# FluxamasynthParticleTeensy.net
KiCad netlist of a schematic drawn in EAGLE
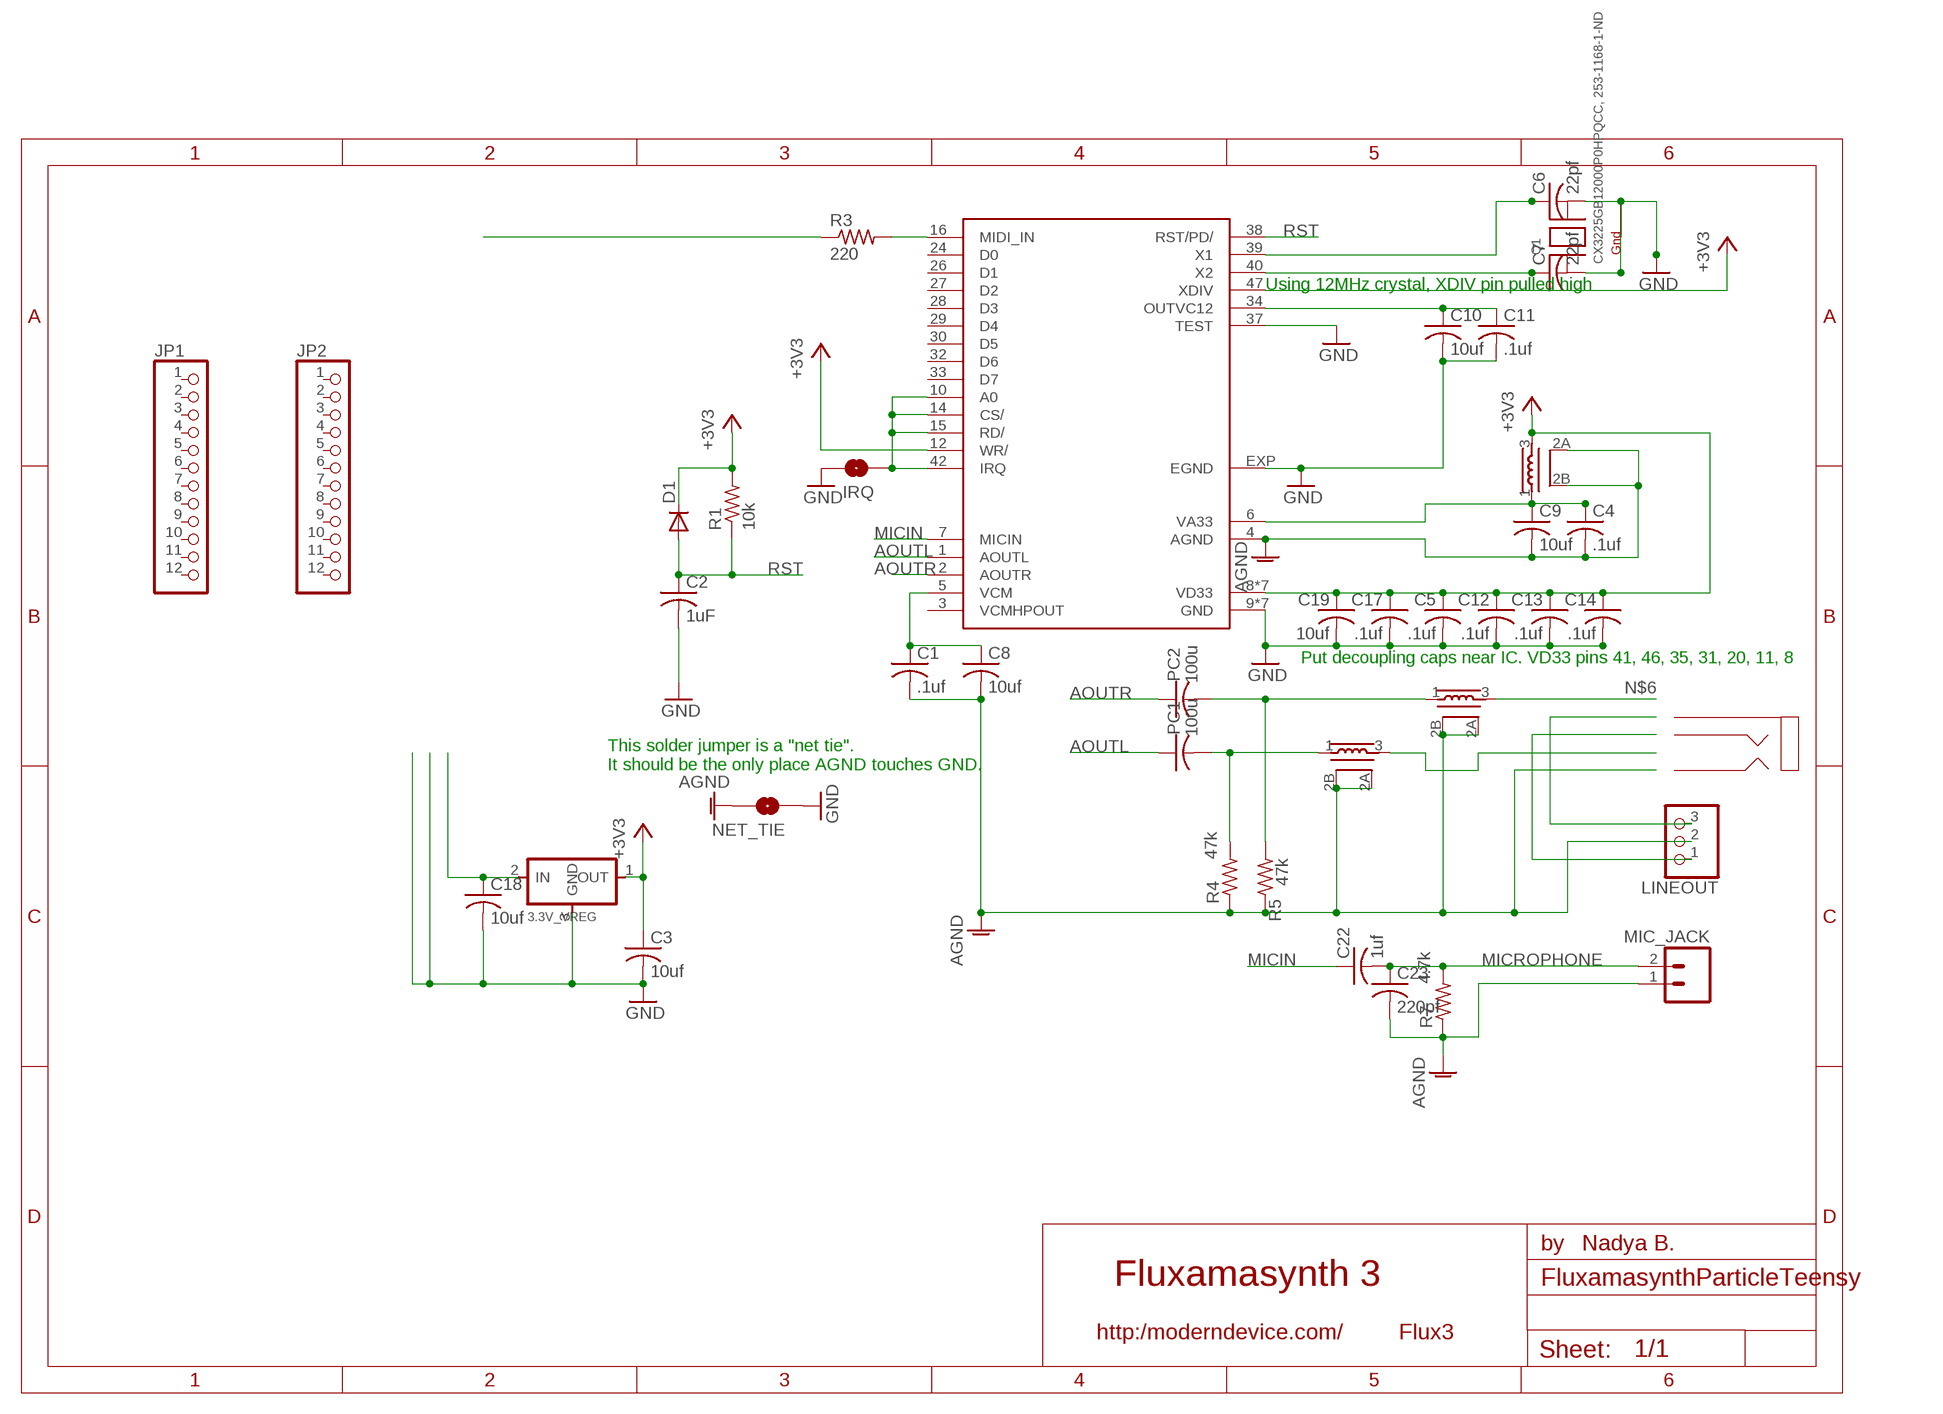
[diagram p0: schematic, sheet 1]

(export (version "E")
  (design (tool "Eeschema 10.0.6"))
  (components
    (comp (ref "3.3V_VREG")
      (value "REGULATORSOT23")
      (footprint "eagle-import:SOT23")
      (libsource (lib "eagle-import") (part "REGULATORSOT23"))
    )
    (comp (ref "C1")
      (value ".1uf")
      (footprint "eagle-import:C0603K")
      (libsource (lib "eagle-import") (part "rcl_C-USC0603K"))
    )
    (comp (ref "C2")
      (value "1uF")
      (footprint "eagle-import:C0805")
      (libsource (lib "eagle-import") (part "rcl_C-USC0805"))
    )
    (comp (ref "C3")
      (value "10uf")
      (footprint "eagle-import:C1206K")
      (libsource (lib "eagle-import") (part "C-USC1206K"))
    )
    (comp (ref "C4")
      (value ".1uf")
      (footprint "eagle-import:C0603K")
      (libsource (lib "eagle-import") (part "rcl_C-USC0603K"))
    )
    (comp (ref "C5")
      (value ".1uf")
      (footprint "eagle-import:C0603K")
      (libsource (lib "eagle-import") (part "rcl_C-USC0603K"))
    )
    (comp (ref "C6")
      (value "22pf")
      (footprint "eagle-import:C0805")
      (libsource (lib "eagle-import") (part "rcl_C-USC0805"))
    )
    (comp (ref "C7")
      (value "22pf")
      (footprint "eagle-import:C0805")
      (libsource (lib "eagle-import") (part "rcl_C-USC0805"))
    )
    (comp (ref "C8")
      (value "10uf")
      (footprint "eagle-import:C0805")
      (libsource (lib "eagle-import") (part "rcl_C-USC0805"))
    )
    (comp (ref "C9")
      (value "10uf")
      (footprint "eagle-import:C0805")
      (libsource (lib "eagle-import") (part "rcl_C-USC0805"))
    )
    (comp (ref "C10")
      (value "10uf")
      (footprint "eagle-import:C0805")
      (libsource (lib "eagle-import") (part "rcl_C-USC0805"))
    )
    (comp (ref "C11")
      (value ".1uf")
      (footprint "eagle-import:C0603K")
      (libsource (lib "eagle-import") (part "rcl_C-USC0603K"))
    )
    (comp (ref "C12")
      (value ".1uf")
      (footprint "eagle-import:C0603K")
      (libsource (lib "eagle-import") (part "rcl_C-USC0603K"))
    )
    (comp (ref "C13")
      (value ".1uf")
      (footprint "eagle-import:C0603K")
      (libsource (lib "eagle-import") (part "rcl_C-USC0603K"))
    )
    (comp (ref "C14")
      (value ".1uf")
      (footprint "eagle-import:C0603K")
      (libsource (lib "eagle-import") (part "rcl_C-USC0603K"))
    )
    (comp (ref "C17")
      (value ".1uf")
      (footprint "eagle-import:C0603K")
      (libsource (lib "eagle-import") (part "rcl_C-USC0603K"))
    )
    (comp (ref "C18")
      (value "10uf")
      (footprint "eagle-import:C1206K")
      (libsource (lib "eagle-import") (part "C-USC1206K"))
    )
    (comp (ref "C19")
      (value "10uf")
      (footprint "eagle-import:C0805")
      (libsource (lib "eagle-import") (part "rcl_C-USC0805"))
    )
    (comp (ref "C22")
      (value "1uf")
      (footprint "eagle-import:C0805")
      (libsource (lib "eagle-import") (part "rcl_C-USC0805"))
    )
    (comp (ref "C23")
      (value "220pf")
      (footprint "eagle-import:C0805")
      (libsource (lib "eagle-import") (part "rcl_C-USC0805"))
    )
    (comp (ref "D1")
      (value "DIODESOD123")
      (footprint "eagle-import:SOD123")
      (libsource (lib "eagle-import") (part "DIODESOD123"))
    )
    (comp (ref "IRQ")
      (value "MODERNDEVICE_SOLDERJUMPERTRACE")
      (footprint "eagle-import:MODERNDEVICE_SJ_2S-TRACE")
      (libsource (lib "eagle-import") (part "MODERNDEVICE_SOLDERJUMPERTRACE"))
    )
    (comp (ref "JP1")
      (value "PINHD-1X12-CB")
      (footprint "eagle-import:1X12-CB")
      (libsource (lib "eagle-import") (part "PINHD-1X12-CB"))
    )
    (comp (ref "JP2")
      (value "PINHD-1X12-CB")
      (footprint "eagle-import:1X12-CB")
      (libsource (lib "eagle-import") (part "PINHD-1X12-CB"))
    )
    (comp (ref "LINEOUT")
      (value "PINHD-1X3")
      (footprint "eagle-import:1X03")
      (libsource (lib "eagle-import") (part "PINHD-1X3"))
    )
    (comp (ref "MIC_JACK")
      (value "M02PTH")
      (footprint "eagle-import:1X02")
      (libsource (lib "eagle-import") (part "M02PTH"))
    )
    (comp (ref "NET_TIE")
      (value "MODERNDEVICE_SOLDERJUMPERTRACE")
      (footprint "eagle-import:MODERNDEVICE_SJ_2S-TRACE")
      (libsource (lib "eagle-import") (part "MODERNDEVICE_SOLDERJUMPERTRACE"))
    )
    (comp (ref "PC1")
      (value "100u")
      (footprint "eagle-import:C1206K")
      (libsource (lib "eagle-import") (part "C-USC1206K"))
    )
    (comp (ref "PC2")
      (value "100u")
      (footprint "eagle-import:C1206K")
      (libsource (lib "eagle-import") (part "C-USC1206K"))
    )
    (comp (ref "Q1")
      (value "CX3225GB12000P0HPQCC, 253-1168-1-ND")
      (footprint "eagle-import:MODERNDEVICE_NX3225")
      (libsource (lib "eagle-import") (part "MODERNDEVICE_XTAL-4-3225"))
    )
    (comp (ref "R1")
      (value "10k")
      (footprint "eagle-import:M0805")
      (libsource (lib "eagle-import") (part "R-US_M0805"))
    )
    (comp (ref "R3")
      (value "220")
      (footprint "eagle-import:M0805")
      (libsource (lib "eagle-import") (part "R-US_M0805"))
    )
    (comp (ref "R4")
      (value "47k")
      (footprint "eagle-import:R0603")
      (libsource (lib "eagle-import") (part "R-US_R0603"))
    )
    (comp (ref "R5")
      (value "47k")
      (footprint "eagle-import:R0603")
      (libsource (lib "eagle-import") (part "R-US_R0603"))
    )
    (comp (ref "R7")
      (value "4.7k")
      (footprint "eagle-import:M0805")
      (libsource (lib "eagle-import") (part "R-US_M0805"))
    )
    (comp (ref "SAM2695")
      (value "SAM2695")
      (footprint "eagle-import:QFN48")
      (libsource (lib "eagle-import") (part "SAM2695"))
    )
    (comp (ref "U$1")
      (value "STEREO_AUDIO_JACK_SMT")
      (footprint "eagle-import:STEREO_AUDIO_JACK_SMT")
      (libsource (lib "eagle-import") (part "STEREO_AUDIO_JACK_SMT"))
    )
    (comp (ref "U$4")
      (value "NFM21CC223R1H3D")
      (footprint "eagle-import:3PC")
      (libsource (lib "eagle-import") (part "NFM21CC223R1H3D"))
    )
    (comp (ref "U$5")
      (value "NFM21CC223R1H3D")
      (footprint "eagle-import:3PC")
      (libsource (lib "eagle-import") (part "NFM21CC223R1H3D"))
    )
    (comp (ref "U$7")
      (value "NFM21CC223R1H3D")
      (footprint "eagle-import:3PC")
      (libsource (lib "eagle-import") (part "NFM21CC223R1H3D"))
    )
  )
  (nets
    (net (code "1") (name "+3V3") (class "Default")
      (node (ref "3.3V_VREG") (pin "1") (pinfunction "OUT_1") (pintype "bidirectional"))
      (node (ref "C12") (pin "1") (pinfunction "1_1") (pintype "passive"))
      (node (ref "C13") (pin "1") (pinfunction "1_1") (pintype "passive"))
      (node (ref "C14") (pin "1") (pinfunction "1_1") (pintype "passive"))
      (node (ref "C17") (pin "1") (pinfunction "1_1") (pintype "passive"))
      (node (ref "C19") (pin "1") (pinfunction "1_1") (pintype "passive"))
      (node (ref "C3") (pin "1") (pinfunction "1_1") (pintype "passive"))
      (node (ref "C5") (pin "1") (pinfunction "1_1") (pintype "passive"))
      (node (ref "D1") (pin "CATHODE") (pinfunction "C_CATHODE") (pintype "passive"))
      (node (ref "R1") (pin "2") (pinfunction "2_2") (pintype "passive"))
      (node (ref "SAM2695") (pin "11") (pinfunction "VD33_11") (pintype "power_in"))
      (node (ref "SAM2695") (pin "12") (pinfunction "WR/_12") (pintype "input"))
      (node (ref "SAM2695") (pin "20") (pinfunction "VD33_20") (pintype "power_in"))
      (node (ref "SAM2695") (pin "31") (pinfunction "VD33_31") (pintype "power_in"))
      (node (ref "SAM2695") (pin "35") (pinfunction "VD33_35") (pintype "power_in"))
      (node (ref "SAM2695") (pin "41") (pinfunction "VD33_41") (pintype "power_in"))
      (node (ref "SAM2695") (pin "46") (pinfunction "VD33_46") (pintype "power_in"))
      (node (ref "SAM2695") (pin "47") (pinfunction "XDIV_47") (pintype "input"))
      (node (ref "SAM2695") (pin "8") (pinfunction "VD33_8") (pintype "power_in"))
      (node (ref "U$7") (pin "3") (pinfunction "3_3") (pintype "bidirectional"))
    )
    (net (code "2") (name "/AOUTL") (class "Default")
      (node (ref "PC1") (pin "1") (pinfunction "1_1") (pintype "passive"))
      (node (ref "SAM2695") (pin "1") (pinfunction "AOUTL_1") (pintype "output"))
    )
    (net (code "3") (name "/AOUTR") (class "Default")
      (node (ref "PC2") (pin "1") (pinfunction "1_1") (pintype "passive"))
      (node (ref "SAM2695") (pin "2") (pinfunction "AOUTR_2") (pintype "output"))
    )
    (net (code "4") (name "/MICIN") (class "Default")
      (node (ref "C22") (pin "1") (pinfunction "1_1") (pintype "passive"))
      (node (ref "SAM2695") (pin "7") (pinfunction "MICIN_7") (pintype "input"))
    )
    (net (code "5") (name "/MICROPHONE") (class "Default")
      (node (ref "C22") (pin "2") (pinfunction "2_2") (pintype "passive"))
      (node (ref "C23") (pin "1") (pinfunction "1_1") (pintype "passive"))
      (node (ref "MIC_JACK") (pin "2") (pinfunction "2_2") (pintype "passive"))
      (node (ref "R7") (pin "2") (pinfunction "2_2") (pintype "passive"))
    )
    (net (code "6") (name "/N$6") (class "Default")
      (node (ref "U$4") (pin "3") (pinfunction "3_3") (pintype "bidirectional"))
    )
    (net (code "7") (name "/RST") (class "Default")
      (node (ref "C2") (pin "1") (pinfunction "1_1") (pintype "passive"))
      (node (ref "D1") (pin "ANODE") (pinfunction "A_ANODE") (pintype "passive"))
      (node (ref "R1") (pin "1") (pinfunction "1_1") (pintype "passive"))
      (node (ref "SAM2695") (pin "38") (pinfunction "RST/PD/_38") (pintype "input"))
    )
    (net (code "8") (name "AGND") (class "Default")
      (node (ref "C1") (pin "2") (pinfunction "2_2") (pintype "passive"))
      (node (ref "C23") (pin "2") (pinfunction "2_2") (pintype "passive"))
      (node (ref "C4") (pin "2") (pinfunction "2_2") (pintype "passive"))
      (node (ref "C8") (pin "2") (pinfunction "2_2") (pintype "passive"))
      (node (ref "C9") (pin "2") (pinfunction "2_2") (pintype "passive"))
      (node (ref "LINEOUT") (pin "2") (pinfunction "2_2") (pintype "passive"))
      (node (ref "MIC_JACK") (pin "1") (pinfunction "1_1") (pintype "passive"))
      (node (ref "NET_TIE") (pin "2") (pinfunction "2_2") (pintype "passive"))
      (node (ref "R4") (pin "1") (pinfunction "1_1") (pintype "passive"))
      (node (ref "R5") (pin "1") (pinfunction "1_1") (pintype "passive"))
      (node (ref "R7") (pin "1") (pinfunction "1_1") (pintype "passive"))
      (node (ref "SAM2695") (pin "4") (pinfunction "AGND_4") (pintype "power_in"))
      (node (ref "U$4") (pin "2A") (pinfunction "2A_2A") (pintype "power_in"))
      (node (ref "U$4") (pin "2B") (pinfunction "2B_2B") (pintype "power_in"))
      (node (ref "U$5") (pin "2A") (pinfunction "2A_2A") (pintype "power_in"))
      (node (ref "U$5") (pin "2B") (pinfunction "2B_2B") (pintype "power_in"))
      (node (ref "U$7") (pin "2A") (pinfunction "2A_2A") (pintype "power_in"))
      (node (ref "U$7") (pin "2B") (pinfunction "2B_2B") (pintype "power_in"))
    )
    (net (code "9") (name "GND") (class "Default")
      (node (ref "3.3V_VREG") (pin "3") (pinfunction "GND_3") (pintype "bidirectional"))
      (node (ref "C10") (pin "2") (pinfunction "2_2") (pintype "passive"))
      (node (ref "C11") (pin "2") (pinfunction "2_2") (pintype "passive"))
      (node (ref "C12") (pin "2") (pinfunction "2_2") (pintype "passive"))
      (node (ref "C13") (pin "2") (pinfunction "2_2") (pintype "passive"))
      (node (ref "C14") (pin "2") (pinfunction "2_2") (pintype "passive"))
      (node (ref "C17") (pin "2") (pinfunction "2_2") (pintype "passive"))
      (node (ref "C18") (pin "2") (pinfunction "2_2") (pintype "passive"))
      (node (ref "C19") (pin "2") (pinfunction "2_2") (pintype "passive"))
      (node (ref "C2") (pin "2") (pinfunction "2_2") (pintype "passive"))
      (node (ref "C3") (pin "2") (pinfunction "2_2") (pintype "passive"))
      (node (ref "C5") (pin "2") (pinfunction "2_2") (pintype "passive"))
      (node (ref "C6") (pin "2") (pinfunction "2_2") (pintype "passive"))
      (node (ref "C7") (pin "2") (pinfunction "2_2") (pintype "passive"))
      (node (ref "IRQ") (pin "2") (pinfunction "2_2") (pintype "passive"))
      (node (ref "NET_TIE") (pin "1") (pinfunction "1_1") (pintype "passive"))
      (node (ref "Q1") (pin "2") (pinfunction "G2_2") (pintype "power_in"))
      (node (ref "Q1") (pin "4") (pinfunction "G1_4") (pintype "power_in"))
      (node (ref "SAM2695") (pin "13") (pinfunction "GND_13") (pintype "power_in"))
      (node (ref "SAM2695") (pin "18") (pinfunction "GND_18") (pintype "power_in"))
      (node (ref "SAM2695") (pin "25") (pinfunction "GND_25") (pintype "power_in"))
      (node (ref "SAM2695") (pin "36") (pinfunction "GND_36") (pintype "power_in"))
      (node (ref "SAM2695") (pin "37") (pinfunction "TEST_37") (pintype "input"))
      (node (ref "SAM2695") (pin "45") (pinfunction "GND_45") (pintype "power_in"))
      (node (ref "SAM2695") (pin "48") (pinfunction "GND_48") (pintype "power_in"))
      (node (ref "SAM2695") (pin "9") (pinfunction "GND_9") (pintype "power_in"))
      (node (ref "SAM2695") (pin "EXP") (pinfunction "EGND_EXP") (pintype "power_in"))
    )
    (net (code "10") (name "Net-(3.3V_VREG-IN)") (class "Default")
      (node (ref "3.3V_VREG") (pin "2") (pinfunction "IN_2") (pintype "bidirectional"))
      (node (ref "C18") (pin "1") (pinfunction "1_1") (pintype "passive"))
    )
    (net (code "11") (name "Net-(PC1-Pad2)") (class "Default")
      (node (ref "PC1") (pin "2") (pinfunction "2_2") (pintype "passive"))
      (node (ref "R4") (pin "2") (pinfunction "2_2") (pintype "passive"))
      (node (ref "U$5") (pin "1") (pinfunction "1_1") (pintype "bidirectional"))
    )
    (net (code "12") (name "Net-(PC2-Pad2)") (class "Default")
      (node (ref "PC2") (pin "2") (pinfunction "2_2") (pintype "passive"))
      (node (ref "R5") (pin "2") (pinfunction "2_2") (pintype "passive"))
      (node (ref "U$4") (pin "1") (pinfunction "1_1") (pintype "bidirectional"))
    )
    (net (code "13") (name "Net-(SAM2695-A0)") (class "Default")
      (node (ref "IRQ") (pin "1") (pinfunction "1_1") (pintype "passive"))
      (node (ref "SAM2695") (pin "10") (pinfunction "A0_10") (pintype "input"))
      (node (ref "SAM2695") (pin "14") (pinfunction "CS/_14") (pintype "input"))
      (node (ref "SAM2695") (pin "15") (pinfunction "RD/_15") (pintype "input"))
      (node (ref "SAM2695") (pin "42") (pinfunction "IRQ_42") (pintype "output"))
    )
    (net (code "14") (name "Net-(SAM2695-MIDI_IN)") (class "Default")
      (node (ref "R3") (pin "2") (pinfunction "2_2") (pintype "passive"))
      (node (ref "SAM2695") (pin "16") (pinfunction "MIDI_IN_16") (pintype "input"))
    )
    (net (code "15") (name "Net-(SAM2695-OUTVC12)") (class "Default")
      (node (ref "C10") (pin "1") (pinfunction "1_1") (pintype "passive"))
      (node (ref "C11") (pin "1") (pinfunction "1_1") (pintype "passive"))
      (node (ref "SAM2695") (pin "34") (pinfunction "OUTVC12_34") (pintype "power_in"))
    )
    (net (code "16") (name "Net-(SAM2695-VA33)") (class "Default")
      (node (ref "C4") (pin "1") (pinfunction "1_1") (pintype "passive"))
      (node (ref "C9") (pin "1") (pinfunction "1_1") (pintype "passive"))
      (node (ref "SAM2695") (pin "6") (pinfunction "VA33_6") (pintype "power_in"))
      (node (ref "U$7") (pin "1") (pinfunction "1_1") (pintype "bidirectional"))
    )
    (net (code "17") (name "Net-(SAM2695-VCM)") (class "Default")
      (node (ref "C1") (pin "1") (pinfunction "1_1") (pintype "passive"))
      (node (ref "C8") (pin "1") (pinfunction "1_1") (pintype "passive"))
      (node (ref "SAM2695") (pin "5") (pinfunction "VCM_5") (pintype "output"))
    )
    (net (code "18") (name "Net-(SAM2695-X1)") (class "Default")
      (node (ref "C6") (pin "1") (pinfunction "1_1") (pintype "passive"))
      (node (ref "SAM2695") (pin "39") (pinfunction "X1_39") (pintype "bidirectional"))
    )
    (net (code "19") (name "Net-(SAM2695-X2)") (class "Default")
      (node (ref "C7") (pin "1") (pinfunction "1_1") (pintype "passive"))
      (node (ref "SAM2695") (pin "40") (pinfunction "X2_40") (pintype "bidirectional"))
    )
    (net (code "20") (name "unconnected-(JP1-Pad1)") (class "Default")
      (node (ref "JP1") (pin "1") (pinfunction "1_1") (pintype "passive"))
    )
    (net (code "21") (name "unconnected-(JP1-Pad2)") (class "Default")
      (node (ref "JP1") (pin "2") (pinfunction "2_2") (pintype "passive"))
    )
    (net (code "22") (name "unconnected-(JP1-Pad3)") (class "Default")
      (node (ref "JP1") (pin "3") (pinfunction "3_3") (pintype "passive"))
    )
    (net (code "23") (name "unconnected-(JP1-Pad4)") (class "Default")
      (node (ref "JP1") (pin "4") (pinfunction "4_4") (pintype "passive"))
    )
    (net (code "24") (name "unconnected-(JP1-Pad5)") (class "Default")
      (node (ref "JP1") (pin "5") (pinfunction "5_5") (pintype "passive"))
    )
    (net (code "25") (name "unconnected-(JP1-Pad6)") (class "Default")
      (node (ref "JP1") (pin "6") (pinfunction "6_6") (pintype "passive"))
    )
    (net (code "26") (name "unconnected-(JP1-Pad7)") (class "Default")
      (node (ref "JP1") (pin "7") (pinfunction "7_7") (pintype "passive"))
    )
    (net (code "27") (name "unconnected-(JP1-Pad8)") (class "Default")
      (node (ref "JP1") (pin "8") (pinfunction "8_8") (pintype "passive"))
    )
    (net (code "28") (name "unconnected-(JP1-Pad9)") (class "Default")
      (node (ref "JP1") (pin "9") (pinfunction "9_9") (pintype "passive"))
    )
    (net (code "29") (name "unconnected-(JP1-Pad10)") (class "Default")
      (node (ref "JP1") (pin "10") (pinfunction "10_10") (pintype "passive"))
    )
    (net (code "30") (name "unconnected-(JP1-Pad11)") (class "Default")
      (node (ref "JP1") (pin "11") (pinfunction "11_11") (pintype "passive"))
    )
    (net (code "31") (name "unconnected-(JP1-Pad12)") (class "Default")
      (node (ref "JP1") (pin "12") (pinfunction "12_12") (pintype "passive"))
    )
    (net (code "32") (name "unconnected-(JP2-Pad1)") (class "Default")
      (node (ref "JP2") (pin "1") (pinfunction "1_1") (pintype "passive"))
    )
    (net (code "33") (name "unconnected-(JP2-Pad2)") (class "Default")
      (node (ref "JP2") (pin "2") (pinfunction "2_2") (pintype "passive"))
    )
    (net (code "34") (name "unconnected-(JP2-Pad3)") (class "Default")
      (node (ref "JP2") (pin "3") (pinfunction "3_3") (pintype "passive"))
    )
    (net (code "35") (name "unconnected-(JP2-Pad4)") (class "Default")
      (node (ref "JP2") (pin "4") (pinfunction "4_4") (pintype "passive"))
    )
    (net (code "36") (name "unconnected-(JP2-Pad5)") (class "Default")
      (node (ref "JP2") (pin "5") (pinfunction "5_5") (pintype "passive"))
    )
    (net (code "37") (name "unconnected-(JP2-Pad6)") (class "Default")
      (node (ref "JP2") (pin "6") (pinfunction "6_6") (pintype "passive"))
    )
    (net (code "38") (name "unconnected-(JP2-Pad7)") (class "Default")
      (node (ref "JP2") (pin "7") (pinfunction "7_7") (pintype "passive"))
    )
    (net (code "39") (name "unconnected-(JP2-Pad8)") (class "Default")
      (node (ref "JP2") (pin "8") (pinfunction "8_8") (pintype "passive"))
    )
    (net (code "40") (name "unconnected-(JP2-Pad9)") (class "Default")
      (node (ref "JP2") (pin "9") (pinfunction "9_9") (pintype "passive"))
    )
    (net (code "41") (name "unconnected-(JP2-Pad10)") (class "Default")
      (node (ref "JP2") (pin "10") (pinfunction "10_10") (pintype "passive"))
    )
    (net (code "42") (name "unconnected-(JP2-Pad11)") (class "Default")
      (node (ref "JP2") (pin "11") (pinfunction "11_11") (pintype "passive"))
    )
    (net (code "43") (name "unconnected-(JP2-Pad12)") (class "Default")
      (node (ref "JP2") (pin "12") (pinfunction "12_12") (pintype "passive"))
    )
    (net (code "44") (name "unconnected-(LINEOUT-Pad1)") (class "Default")
      (node (ref "LINEOUT") (pin "1") (pinfunction "1_1") (pintype "passive"))
    )
    (net (code "45") (name "unconnected-(LINEOUT-Pad3)") (class "Default")
      (node (ref "LINEOUT") (pin "3") (pinfunction "3_3") (pintype "passive"))
    )
    (net (code "46") (name "unconnected-(Q1-X1-Pad1)") (class "Default")
      (node (ref "Q1") (pin "1") (pinfunction "X1_1") (pintype "bidirectional"))
    )
    (net (code "47") (name "unconnected-(Q1-X2-Pad3)") (class "Default")
      (node (ref "Q1") (pin "3") (pinfunction "X2_3") (pintype "bidirectional"))
    )
    (net (code "48") (name "unconnected-(R3-Pad1)") (class "Default")
      (node (ref "R3") (pin "1") (pinfunction "1_1") (pintype "passive"))
    )
    (net (code "49") (name "unconnected-(SAM2695-D0-Pad24)") (class "Default")
      (node (ref "SAM2695") (pin "24") (pinfunction "D0_24") (pintype "bidirectional"))
    )
    (net (code "50") (name "unconnected-(SAM2695-D1-Pad26)") (class "Default")
      (node (ref "SAM2695") (pin "26") (pinfunction "D1_26") (pintype "bidirectional"))
    )
    (net (code "51") (name "unconnected-(SAM2695-D2-Pad27)") (class "Default")
      (node (ref "SAM2695") (pin "27") (pinfunction "D2_27") (pintype "bidirectional"))
    )
    (net (code "52") (name "unconnected-(SAM2695-D3-Pad28)") (class "Default")
      (node (ref "SAM2695") (pin "28") (pinfunction "D3_28") (pintype "bidirectional"))
    )
    (net (code "53") (name "unconnected-(SAM2695-D4-Pad29)") (class "Default")
      (node (ref "SAM2695") (pin "29") (pinfunction "D4_29") (pintype "bidirectional"))
    )
    (net (code "54") (name "unconnected-(SAM2695-D5-Pad30)") (class "Default")
      (node (ref "SAM2695") (pin "30") (pinfunction "D5_30") (pintype "bidirectional"))
    )
    (net (code "55") (name "unconnected-(SAM2695-D6-Pad32)") (class "Default")
      (node (ref "SAM2695") (pin "32") (pinfunction "D6_32") (pintype "bidirectional"))
    )
    (net (code "56") (name "unconnected-(SAM2695-D7-Pad33)") (class "Default")
      (node (ref "SAM2695") (pin "33") (pinfunction "D7_33") (pintype "bidirectional"))
    )
    (net (code "57") (name "unconnected-(SAM2695-VCMHPOUT-Pad3)") (class "Default")
      (node (ref "SAM2695") (pin "3") (pinfunction "VCMHPOUT_3") (pintype "output"))
    )
    (net (code "58") (name "unconnected-(U$1-RING-PadP$3)") (class "Default")
      (node (ref "U$1") (pin "P$3") (pinfunction "RING_P$3") (pintype "bidirectional"))
    )
    (net (code "59") (name "unconnected-(U$1-SHIELD-PadP$1)") (class "Default")
      (node (ref "U$1") (pin "P$1") (pinfunction "SHIELD_P$1") (pintype "bidirectional"))
    )
    (net (code "60") (name "unconnected-(U$1-TIP-PadP$2)") (class "Default")
      (node (ref "U$1") (pin "P$2") (pinfunction "TIP_P$2") (pintype "bidirectional"))
    )
    (net (code "61") (name "unconnected-(U$5-Pad3)") (class "Default")
      (node (ref "U$5") (pin "3") (pinfunction "3_3") (pintype "bidirectional"))
    )
  )
)
